# B2_RAD_FPGA.net
KiCad netlist of a schematic drawn in Altium Designer
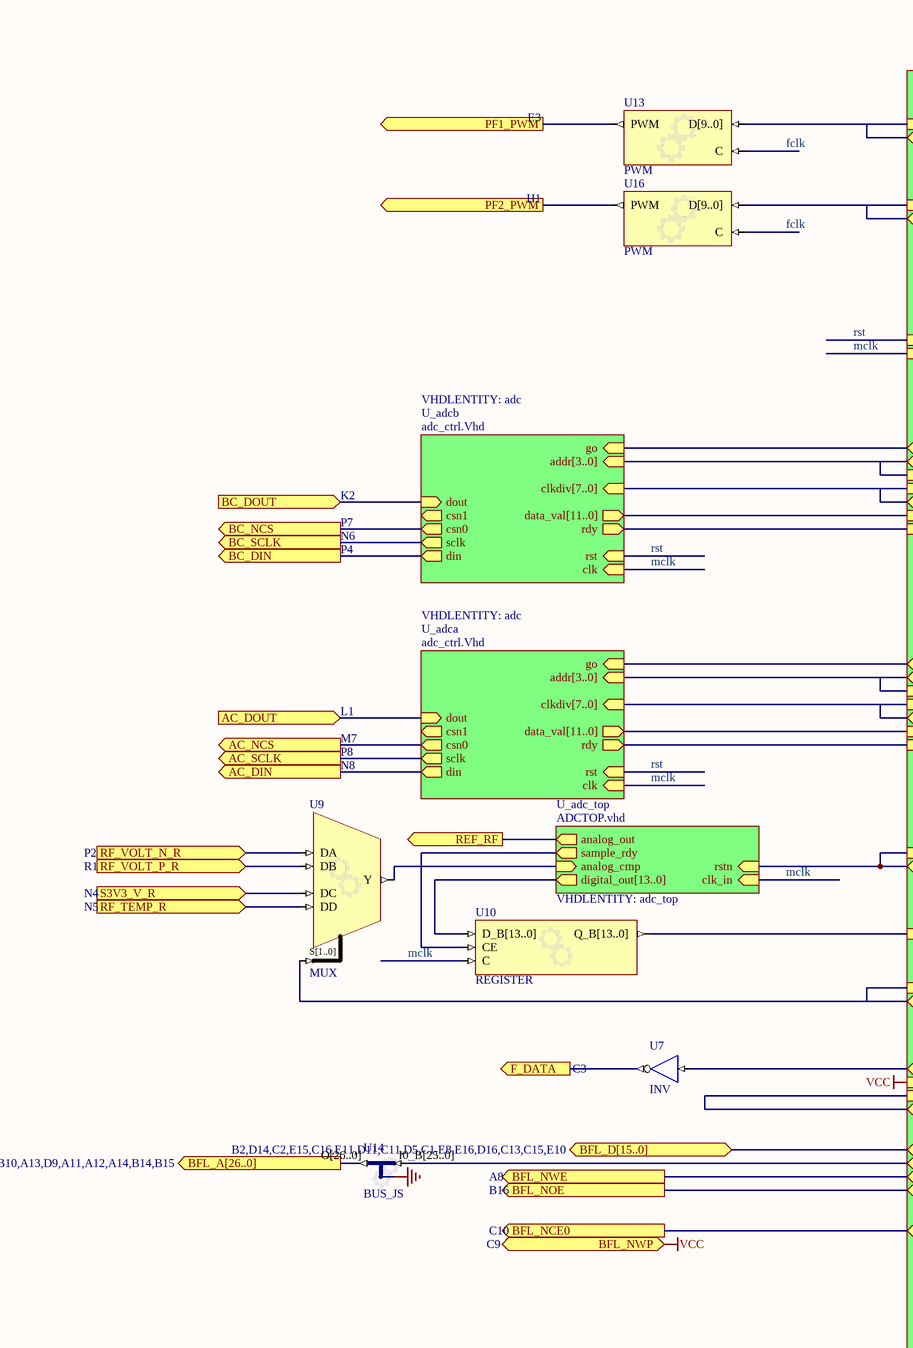
[diagram p0: B2_RAD_FPGA.SchDoc, left]
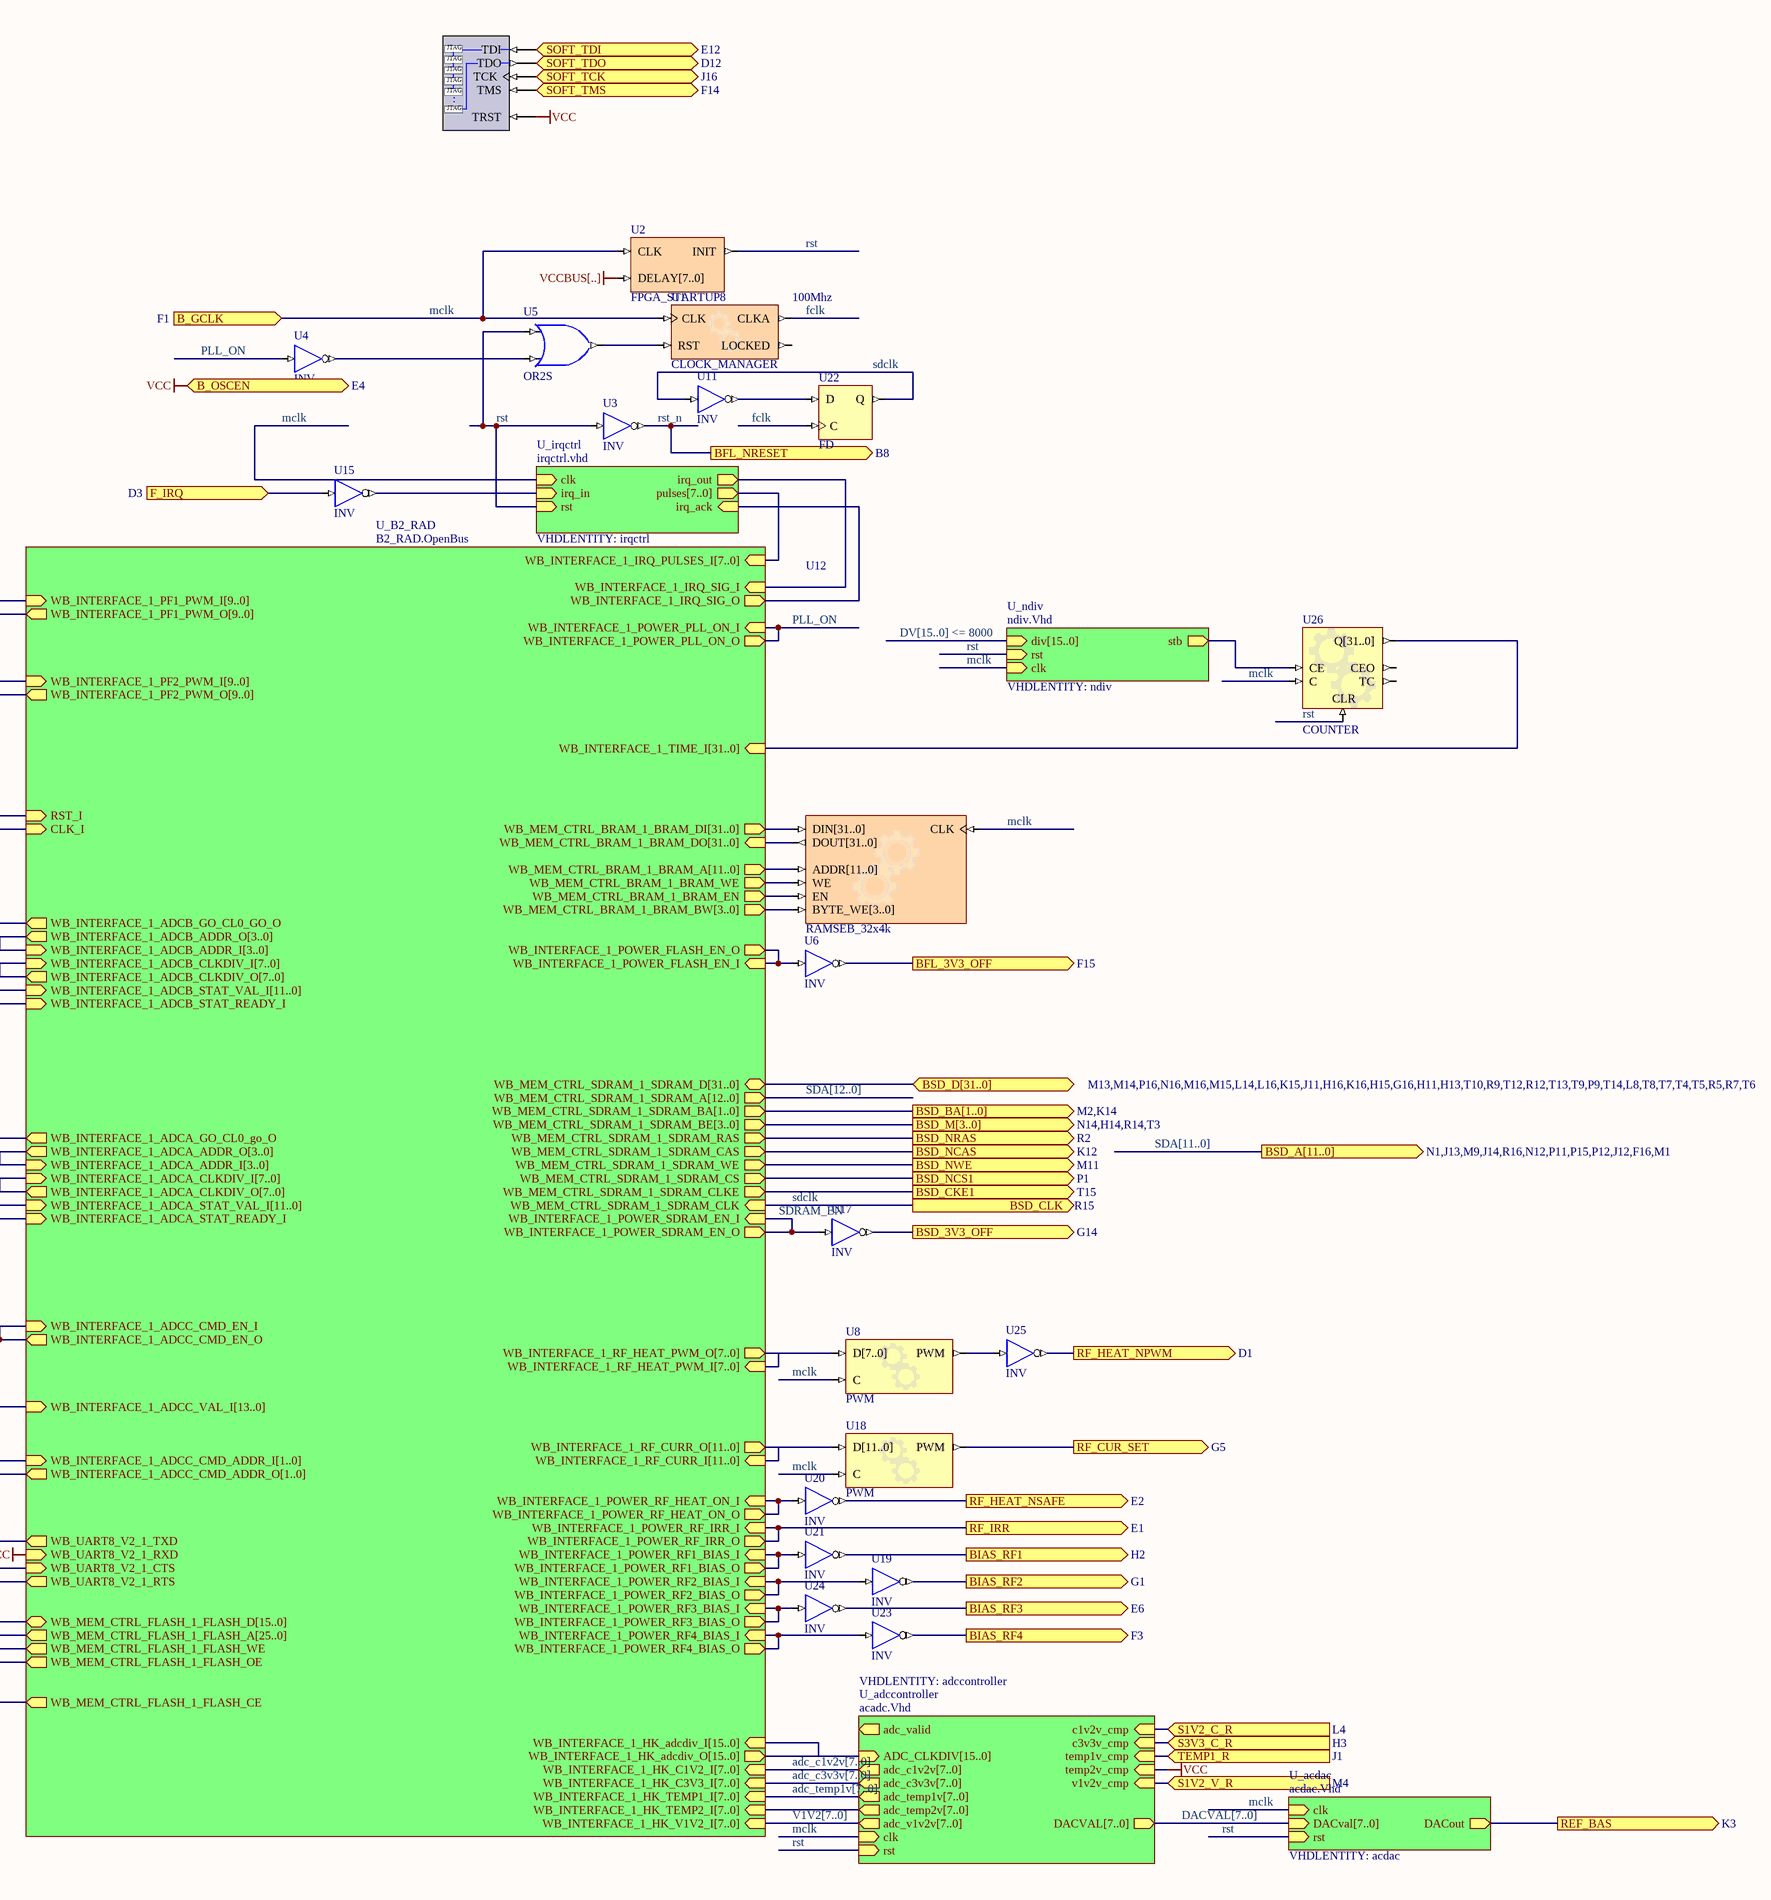
[diagram p1: B2_RAD_FPGA.SchDoc, right]

(export (version "E")
  (design (tool "Eeschema 10.0.6"))
  (components
    (comp (ref "NEXUS_JTAG_PORT")
      (value "NEXUS_JTAG_PORT")
      (description "Soft Nexus-Chain Connector")
      (fields (field (name "PUBLISHER") "Altium Limited"))
      (libsource (lib "FPGA Generic") (part "NEXUS_JTAG_PORT"))
    )
    (comp (ref "U1")
      (value "CLOCK_MANAGER")
      (description "Configurable Clock Manager")
      (fields (field (name "PUBLISHER") "Altium Limited"))
      (libsource (lib "FPGA Configurable Generic") (part "CLOCKMANAGER"))
    )
    (comp (ref "U2")
      (value "FPGA_STARTUP8")
      (description "FPGA Startup With 8 Bit Delay")
      (fields (field (name "PUBLISHER") "Altium Limited"))
      (libsource (lib "FPGA Generic") (part "FPGA_STARTUP8"))
    )
    (comp (ref "U3")
      (value "INV")
      (description "Inverter")
      (fields (field (name "PUBLISHER") "Altium Limited"))
      (libsource (lib "FPGA Generic") (part "INV"))
    )
    (comp (ref "U4")
      (value "INV")
      (description "Inverter")
      (fields (field (name "PUBLISHER") "Altium Limited"))
      (libsource (lib "FPGA Generic") (part "INV"))
    )
    (comp (ref "U5")
      (value "OR2S")
      (description "2-Input OR Gate, Single Pin Version")
      (fields (field (name "PUBLISHER") "Altium Limited"))
      (libsource (lib "FPGA Generic") (part "OR2S"))
    )
    (comp (ref "U6")
      (value "INV")
      (description "Inverter")
      (fields (field (name "PUBLISHER") "Altium Limited"))
      (libsource (lib "FPGA Generic") (part "INV"))
    )
    (comp (ref "U7")
      (value "INV")
      (description "Inverter")
      (fields (field (name "PUBLISHER") "Altium Limited"))
      (libsource (lib "FPGA Generic") (part "INV"))
    )
    (comp (ref "U8")
      (value "PWM")
      (description "Configurable PWM")
      (fields (field (name "PUBLISHER") "Altium Limited"))
      (libsource (lib "") (part "PWM_2"))
    )
    (comp (ref "U9")
      (value "MUX")
      (description "Configurable Mutliplexer")
      (fields (field (name "PUBLISHER") "Altium Limited"))
      (libsource (lib "FPGA Configurable Generic") (part "MUX"))
    )
    (comp (ref "U10")
      (value "REGISTER")
      (description "Configurable Register")
      (fields (field (name "PUBLISHER") "Altium Limited"))
      (libsource (lib "FPGA Configurable Generic") (part "REGISTER"))
    )
    (comp (ref "U11")
      (value "INV")
      (description "Inverter")
      (fields (field (name "PUBLISHER") "Altium Limited"))
      (libsource (lib "FPGA Generic") (part "INV"))
    )
    (comp (ref "U12")
      (value "RAMSEB_32x4k")
      (description "Configurable Memory")
      (fields (field (name "PUBLISHER") "Altium Limited"))
      (libsource (lib "FPGA Configurable Generic") (part "MEMORY"))
    )
    (comp (ref "U13")
      (value "PWM")
      (description "Configurable PWM")
      (fields (field (name "PUBLISHER") "Altium Limited"))
      (libsource (lib "") (part "PWM_1"))
    )
    (comp (ref "U14")
      (value "BUS_JS")
      (description "Configurable Bus Joiner/Splitter")
      (fields (field (name "PUBLISHER") "Altium Limited"))
      (libsource (lib "FPGA Configurable Generic") (part "BUS_JS"))
    )
    (comp (ref "U15")
      (value "INV")
      (description "Inverter")
      (fields (field (name "PUBLISHER") "Altium Limited"))
      (libsource (lib "FPGA Generic") (part "INV"))
    )
    (comp (ref "U16")
      (value "PWM")
      (description "Configurable PWM")
      (fields (field (name "PUBLISHER") "Altium Limited"))
      (libsource (lib "") (part "PWM_1"))
    )
    (comp (ref "U17")
      (value "INV")
      (description "Inverter")
      (fields (field (name "PUBLISHER") "Altium Limited"))
      (libsource (lib "FPGA Generic") (part "INV"))
    )
    (comp (ref "U18")
      (value "PWM")
      (description "Configurable PWM")
      (fields (field (name "PUBLISHER") "Altium Limited"))
      (libsource (lib "FPGA Configurable Generic") (part "PWM"))
    )
    (comp (ref "U19")
      (value "INV")
      (description "Inverter")
      (fields (field (name "PUBLISHER") "Altium Limited"))
      (libsource (lib "FPGA Generic") (part "INV"))
    )
    (comp (ref "U20")
      (value "INV")
      (description "Inverter")
      (fields (field (name "PUBLISHER") "Altium Limited"))
      (libsource (lib "FPGA Generic") (part "INV"))
    )
    (comp (ref "U21")
      (value "INV")
      (description "Inverter")
      (fields (field (name "PUBLISHER") "Altium Limited"))
      (libsource (lib "FPGA Generic") (part "INV"))
    )
    (comp (ref "U22")
      (value "FD")
      (description "D-Type Flip-Flop")
      (fields (field (name "PUBLISHER") "Altium Limited"))
      (libsource (lib "FPGA Generic") (part "FD"))
    )
    (comp (ref "U23")
      (value "INV")
      (description "Inverter")
      (fields (field (name "PUBLISHER") "Altium Limited"))
      (libsource (lib "FPGA Generic") (part "INV"))
    )
    (comp (ref "U24")
      (value "INV")
      (description "Inverter")
      (fields (field (name "PUBLISHER") "Altium Limited"))
      (libsource (lib "FPGA Generic") (part "INV"))
    )
    (comp (ref "U25")
      (value "INV")
      (description "Inverter")
      (fields (field (name "PUBLISHER") "Altium Limited"))
      (libsource (lib "FPGA Generic") (part "INV"))
    )
    (comp (ref "U26")
      (value "COUNTER")
      (description "Configurable Counter")
      (fields (field (name "PUBLISHER") "Altium Limited"))
      (libsource (lib "FPGA Configurable Generic") (part "COUNTER"))
    )
  )
  (nets
    (net (code "144") (name "/BFL_3V3_OFF") (class "Default")
      (node (ref "U6") (pin "O") (pinfunction "O_O") (pintype "output"))
    )
    (net (code "145") (name "/BFL_A[26..0]") (class "Default")
      (node (ref "U14") (pin "O[26..0]") (pinfunction "O[26..0]_O[26..0]") (pintype "output"))
    )
    (net (code "150") (name "/BIAS_RF1") (class "Default")
      (node (ref "U21") (pin "O") (pinfunction "O_O") (pintype "output"))
    )
    (net (code "151") (name "/BIAS_RF2") (class "Default")
      (node (ref "U19") (pin "O") (pinfunction "O_O") (pintype "output"))
    )
    (net (code "152") (name "/BIAS_RF3") (class "Default")
      (node (ref "U24") (pin "O") (pinfunction "O_O") (pintype "output"))
    )
    (net (code "153") (name "/BIAS_RF4") (class "Default")
      (node (ref "U23") (pin "O") (pinfunction "O_O") (pintype "output"))
    )
    (net (code "154") (name "/BSD_3V3_OFF") (class "Default")
      (node (ref "U17") (pin "O") (pinfunction "O_O") (pintype "output"))
    )
    (net (code "164") (name "/F_DATA") (class "Default")
      (node (ref "U7") (pin "O") (pinfunction "O_O") (pintype "output"))
    )
    (net (code "165") (name "/F_IRQ") (class "Default")
      (node (ref "U15") (pin "I") (pinfunction "I_I") (pintype "input"))
    )
    (net (code "166") (name "/PF1_PWM") (class "Default")
      (node (ref "U13") (pin "PWM") (pinfunction "PWM_PWM") (pintype "output"))
    )
    (net (code "167") (name "/PF2_PWM") (class "Default")
      (node (ref "U16") (pin "PWM") (pinfunction "PWM_PWM") (pintype "output"))
    )
    (net (code "168") (name "/PLL_ON") (class "Default")
      (node (ref "U4") (pin "I") (pinfunction "I_I") (pintype "input"))
    )
    (net (code "171") (name "/RF_CUR_SET") (class "Default")
      (node (ref "U18") (pin "PWM") (pinfunction "PWM_PWM") (pintype "output"))
    )
    (net (code "172") (name "/RF_HEAT_NPWM") (class "Default")
      (node (ref "U25") (pin "O") (pinfunction "O_O") (pintype "output"))
    )
    (net (code "173") (name "/RF_HEAT_NSAFE") (class "Default")
      (node (ref "U20") (pin "O") (pinfunction "O_O") (pintype "output"))
    )
    (net (code "175") (name "/RF_TEMP_R") (class "Default")
      (node (ref "U9") (pin "DD") (pinfunction "DD_DD") (pintype "input"))
    )
    (net (code "176") (name "/RF_VOLT_N_R") (class "Default")
      (node (ref "U9") (pin "DA") (pinfunction "DA_DA") (pintype "input"))
    )
    (net (code "177") (name "/RF_VOLT_P_R") (class "Default")
      (node (ref "U9") (pin "DB") (pinfunction "DB_DB") (pintype "input"))
    )
    (net (code "181") (name "/S3V3_V_R") (class "Default")
      (node (ref "U9") (pin "DC") (pinfunction "DC_DC") (pintype "input"))
    )
    (net (code "184") (name "/SDRAM_EN") (class "Default")
      (node (ref "U17") (pin "I") (pinfunction "I_I") (pintype "input"))
    )
    (net (code "185") (name "/SOFT_TCK") (class "Default")
      (node (ref "NEXUS_JTAG_PORT") (pin "TCK") (pinfunction "TCK_TCK") (pintype "input"))
    )
    (net (code "186") (name "/SOFT_TDI") (class "Default")
      (node (ref "NEXUS_JTAG_PORT") (pin "TDI") (pinfunction "TDI_TDI") (pintype "input"))
    )
    (net (code "187") (name "/SOFT_TDO") (class "Default")
      (node (ref "NEXUS_JTAG_PORT") (pin "TDO") (pinfunction "TDO_TDO") (pintype "output"))
    )
    (net (code "188") (name "/SOFT_TMS") (class "Default")
      (node (ref "NEXUS_JTAG_PORT") (pin "TMS") (pinfunction "TMS_TMS") (pintype "input"))
    )
    (net (code "200") (name "/WB_INTERFACE_1_ADCC_CMD_ADDR_O[1..0]") (class "Default")
      (node (ref "U9") (pin "S[1..0]") (pinfunction "S[1..0]_S[1..0]") (pintype "input"))
    )
    (net (code "202") (name "/WB_INTERFACE_1_ADCC_VAL_I[13..0]") (class "Default")
      (node (ref "U10") (pin "Q_B[13..0]") (pinfunction "Q_B[13..0]_Q_B[13..0]") (pintype "output"))
    )
    (net (code "205") (name "/WB_INTERFACE_1_PF1_PWM_I[9..0]") (class "Default")
      (node (ref "U13") (pin "D[9..0]") (pinfunction "D[9..0]_D[9..0]") (pintype "input"))
    )
    (net (code "207") (name "/WB_INTERFACE_1_PF2_PWM_I[9..0]") (class "Default")
      (node (ref "U16") (pin "D[9..0]") (pinfunction "D[9..0]_D[9..0]") (pintype "input"))
    )
    (net (code "209") (name "/WB_INTERFACE_1_POWER_FLASH_EN_O") (class "Default")
      (node (ref "U6") (pin "I") (pinfunction "I_I") (pintype "input"))
    )
    (net (code "210") (name "/WB_INTERFACE_1_POWER_RF1_BIAS_O") (class "Default")
      (node (ref "U21") (pin "I") (pinfunction "I_I") (pintype "input"))
    )
    (net (code "211") (name "/WB_INTERFACE_1_POWER_RF2_BIAS_O") (class "Default")
      (node (ref "U19") (pin "I") (pinfunction "I_I") (pintype "input"))
    )
    (net (code "212") (name "/WB_INTERFACE_1_POWER_RF3_BIAS_O") (class "Default")
      (node (ref "U24") (pin "I") (pinfunction "I_I") (pintype "input"))
    )
    (net (code "213") (name "/WB_INTERFACE_1_POWER_RF4_BIAS_O") (class "Default")
      (node (ref "U23") (pin "I") (pinfunction "I_I") (pintype "input"))
    )
    (net (code "214") (name "/WB_INTERFACE_1_POWER_RF_HEAT_ON_O") (class "Default")
      (node (ref "U20") (pin "I") (pinfunction "I_I") (pintype "input"))
    )
    (net (code "216") (name "/WB_INTERFACE_1_RF_CURR_O[11..0]") (class "Default")
      (node (ref "U18") (pin "D[11..0]") (pinfunction "D[11..0]_D[11..0]") (pintype "input"))
    )
    (net (code "218") (name "/WB_INTERFACE_1_RF_HEAT_PWM_O[7..0]") (class "Default")
      (node (ref "U8") (pin "D[7..0]") (pinfunction "D[7..0]_D[7..0]") (pintype "input"))
    )
    (net (code "219") (name "/WB_INTERFACE_1_TIME_I[31..0]") (class "Default")
      (node (ref "U26") (pin "Q[31..0]") (pinfunction "Q[31..0]_Q[31..0]") (pintype "output"))
    )
    (net (code "220") (name "/WB_MEM_CTRL_BRAM_1_BRAM_A[11..0]") (class "Default")
      (node (ref "U12") (pin "ADDR[11..0]") (pinfunction "ADDR[11..0]_ADDR[11..0]") (pintype "input"))
    )
    (net (code "221") (name "/WB_MEM_CTRL_BRAM_1_BRAM_BW[3..0]") (class "Default")
      (node (ref "U12") (pin "BYTE_WE[3..0]") (pinfunction "BYTE_WE[3..0]_BYTE_WE[3..0]") (pintype "input"))
    )
    (net (code "222") (name "/WB_MEM_CTRL_BRAM_1_BRAM_DI[31..0]") (class "Default")
      (node (ref "U12") (pin "DIN[31..0]") (pinfunction "DIN[31..0]_DIN[31..0]") (pintype "input"))
    )
    (net (code "223") (name "/WB_MEM_CTRL_BRAM_1_BRAM_DO[31..0]") (class "Default")
      (node (ref "U12") (pin "DOUT[31..0]") (pinfunction "DOUT[31..0]_DOUT[31..0]") (pintype "output"))
    )
    (net (code "224") (name "/WB_MEM_CTRL_BRAM_1_BRAM_EN") (class "Default")
      (node (ref "U12") (pin "EN") (pinfunction "EN_EN") (pintype "input"))
    )
    (net (code "225") (name "/WB_MEM_CTRL_BRAM_1_BRAM_WE") (class "Default")
      (node (ref "U12") (pin "WE") (pinfunction "WE_WE") (pintype "input"))
    )
    (net (code "226") (name "/WB_MEM_CTRL_FLASH_1_FLASH_A[25..0]") (class "Default")
      (node (ref "U14") (pin "I0_B[25..0]") (pinfunction "I0_B[25..0]_I0_B[25..0]") (pintype "input"))
    )
    (net (code "228") (name "/WB_UART8_V2_1_TXD") (class "Default")
      (node (ref "U7") (pin "I") (pinfunction "I_I") (pintype "input"))
    )
    (net (code "234") (name "/analog_cmp") (class "Default")
      (node (ref "U9") (pin "Y") (pinfunction "Y_Y") (pintype "output"))
    )
    (net (code "239") (name "/digital_out[13..0]") (class "Default")
      (node (ref "U10") (pin "D_B[13..0]") (pinfunction "D_B[13..0]_D_B[13..0]") (pintype "input"))
    )
    (net (code "240") (name "/fclk") (class "Default")
      (node (ref "U1") (pin "CLKA") (pinfunction "CLKA_CLKA") (pintype "output"))
      (node (ref "U13") (pin "C") (pinfunction "C_C") (pintype "input"))
      (node (ref "U16") (pin "C") (pinfunction "C_C") (pintype "input"))
      (node (ref "U22") (pin "C") (pinfunction "C_C") (pintype "input"))
    )
    (net (code "241") (name "/irq_in") (class "Default")
      (node (ref "U15") (pin "O") (pinfunction "O_O") (pintype "output"))
    )
    (net (code "243") (name "/mclk") (class "Default")
      (node (ref "U1") (pin "CLK") (pinfunction "CLK_CLK") (pintype "input"))
      (node (ref "U10") (pin "C") (pinfunction "C_C") (pintype "input"))
      (node (ref "U12") (pin "CLK") (pinfunction "CLK_CLK") (pintype "input"))
      (node (ref "U18") (pin "C") (pinfunction "C_C") (pintype "input"))
      (node (ref "U2") (pin "CLK") (pinfunction "CLK_CLK") (pintype "input"))
      (node (ref "U26") (pin "C") (pinfunction "C_C") (pintype "input"))
      (node (ref "U8") (pin "C") (pinfunction "C_C") (pintype "input"))
    )
    (net (code "247") (name "/rst") (class "Default")
      (node (ref "U2") (pin "INIT") (pinfunction "INIT_INIT") (pintype "output"))
      (node (ref "U26") (pin "CLR") (pinfunction "CLR_CLR") (pintype "input"))
      (node (ref "U3") (pin "I") (pinfunction "I_I") (pintype "input"))
      (node (ref "U5") (pin "I0") (pinfunction "I0_I0") (pintype "input"))
    )
    (net (code "248") (name "/rst_n") (class "Default")
      (node (ref "U3") (pin "O") (pinfunction "O_O") (pintype "output"))
    )
    (net (code "249") (name "/sample_rdy") (class "Default")
      (node (ref "U10") (pin "CE") (pinfunction "CE_CE") (pintype "input"))
    )
    (net (code "250") (name "/sdclk") (class "Default")
      (node (ref "U11") (pin "I") (pinfunction "I_I") (pintype "input"))
      (node (ref "U22") (pin "Q") (pinfunction "Q_Q") (pintype "output"))
    )
    (net (code "251") (name "/stb") (class "Default")
      (node (ref "U26") (pin "CE") (pinfunction "CE_CE") (pintype "input"))
    )
    (net (code "253") (name "GND") (class "Default")
      (node (ref "U14") (pin "I1") (pinfunction "I1_I1") (pintype "input"))
    )
    (net (code "254") (name "Net-(U1-PadRST)") (class "Default")
      (node (ref "U1") (pin "RST") (pinfunction "RST_RST") (pintype "input"))
      (node (ref "U5") (pin "O") (pinfunction "O_O") (pintype "output"))
    )
    (net (code "255") (name "Net-(U4-PadO)") (class "Default")
      (node (ref "U4") (pin "O") (pinfunction "O_O") (pintype "output"))
      (node (ref "U5") (pin "I1") (pinfunction "I1_I1") (pintype "input"))
    )
    (net (code "256") (name "Net-(U11-PadO)") (class "Default")
      (node (ref "U11") (pin "O") (pinfunction "O_O") (pintype "output"))
      (node (ref "U22") (pin "D") (pinfunction "D_D") (pintype "input"))
    )
    (net (code "257") (name "Net-(U25-PadI)") (class "Default")
      (node (ref "U25") (pin "I") (pinfunction "I_I") (pintype "input"))
      (node (ref "U8") (pin "PWM") (pinfunction "PWM_PWM") (pintype "output"))
    )
    (net (code "258") (name "VCC") (class "Default")
      (node (ref "NEXUS_JTAG_PORT") (pin "TRST") (pinfunction "TRST_TRST") (pintype "input"))
    )
    (net (code "259") (name "VCCBUS[..]") (class "Default")
      (node (ref "U2") (pin "DELAY[7..0]") (pinfunction "DELAY[7..0]_DELAY[7..0]") (pintype "input"))
    )
    (net (code "260") (name "unconnected-(U1-PadLOCKED)") (class "Default")
      (node (ref "U1") (pin "LOCKED") (pinfunction "LOCKED_LOCKED") (pintype "output"))
    )
    (net (code "261") (name "unconnected-(U26-PadCEO)") (class "Default")
      (node (ref "U26") (pin "CEO") (pinfunction "CEO_CEO") (pintype "output"))
    )
    (net (code "262") (name "unconnected-(U26-PadTC)") (class "Default")
      (node (ref "U26") (pin "TC") (pinfunction "TC_TC") (pintype "output"))
    )
  )
)
